# LCD-Input_Module.net
KiCad netlist of a schematic drawn in EAGLE
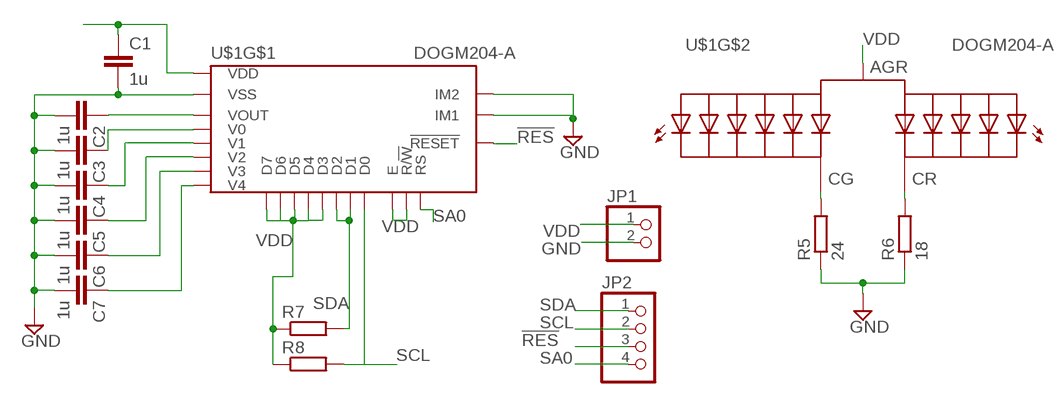
[diagram p0: schematic, sheet 1]
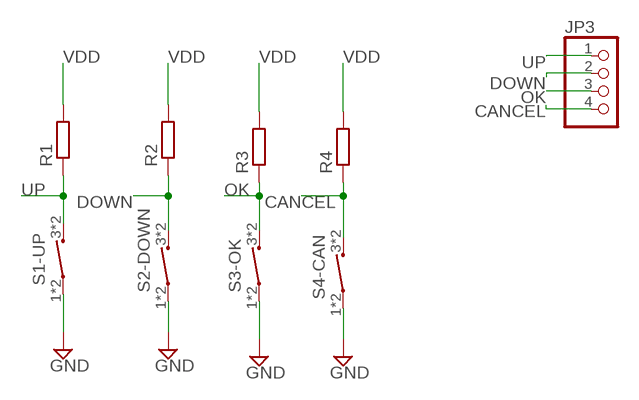
[diagram p1: schematic, sheet 2]

(export (version "E")
  (design (tool "Eeschema 10.0.6"))
  (components
    (comp (ref "C1")
      (value "1u")
      (footprint "eagle-import:C0603")
      (libsource (lib "eagle-import") (part "C-EUC0603"))
    )
    (comp (ref "C2")
      (value "1u")
      (footprint "eagle-import:C0603")
      (libsource (lib "eagle-import") (part "C-EUC0603"))
    )
    (comp (ref "C3")
      (value "1u")
      (footprint "eagle-import:C0603")
      (libsource (lib "eagle-import") (part "C-EUC0603"))
    )
    (comp (ref "C4")
      (value "1u")
      (footprint "eagle-import:C0603")
      (libsource (lib "eagle-import") (part "C-EUC0603"))
    )
    (comp (ref "C5")
      (value "1u")
      (footprint "eagle-import:C0603")
      (libsource (lib "eagle-import") (part "C-EUC0603"))
    )
    (comp (ref "C6")
      (value "1u")
      (footprint "eagle-import:C0603")
      (libsource (lib "eagle-import") (part "C-EUC0603"))
    )
    (comp (ref "C7")
      (value "1u")
      (footprint "eagle-import:C0603")
      (libsource (lib "eagle-import") (part "C-EUC0603"))
    )
    (comp (ref "JP1")
      (value "PINHD-1X2")
      (footprint "eagle-import:1X02")
      (libsource (lib "eagle-import") (part "PINHD-1X2"))
    )
    (comp (ref "JP2")
      (value "PINHD-1X4")
      (footprint "eagle-import:1X04")
      (libsource (lib "eagle-import") (part "PINHD-1X4"))
    )
    (comp (ref "R5")
      (value "24")
      (footprint "eagle-import:R0603")
      (libsource (lib "eagle-import") (part "R-EU_R0603"))
    )
    (comp (ref "R6")
      (value "18")
      (footprint "eagle-import:R0603")
      (libsource (lib "eagle-import") (part "R-EU_R0603"))
    )
    (comp (ref "R7")
      (value "R-EU_R0603")
      (footprint "eagle-import:R0603")
      (libsource (lib "eagle-import") (part "R-EU_R0603"))
    )
    (comp (ref "R8")
      (value "R-EU_R0603")
      (footprint "eagle-import:R0603")
      (libsource (lib "eagle-import") (part "R-EU_R0603"))
    )
    (comp (ref "U$1")
      (value "DOGM204-A")
      (footprint "eagle-import:LCD")
      (libsource (lib "eagle-import") (part "DOGM204-A"))
    )
    (comp (ref "JP3")
      (value "PINHD-1X4")
      (footprint "eagle-import:1X04")
      (libsource (lib "eagle-import") (part "PINHD-1X4"))
    )
    (comp (ref "R1")
      (value "R-EU_R0603")
      (footprint "eagle-import:R0603")
      (libsource (lib "eagle-import") (part "R-EU_R0603"))
    )
    (comp (ref "R2")
      (value "R-EU_R0603")
      (footprint "eagle-import:R0603")
      (libsource (lib "eagle-import") (part "R-EU_R0603"))
    )
    (comp (ref "R3")
      (value "R-EU_R0603")
      (footprint "eagle-import:R0603")
      (libsource (lib "eagle-import") (part "R-EU_R0603"))
    )
    (comp (ref "R4")
      (value "R-EU_R0603")
      (footprint "eagle-import:R0603")
      (libsource (lib "eagle-import") (part "R-EU_R0603"))
    )
    (comp (ref "S1-UP")
      (value "PTS647")
      (footprint "eagle-import:PTS647-TACTSWITCH")
      (libsource (lib "eagle-import") (part "PTS647"))
    )
    (comp (ref "S2-DOWN")
      (value "PTS647")
      (footprint "eagle-import:PTS647-TACTSWITCH")
      (libsource (lib "eagle-import") (part "PTS647"))
    )
    (comp (ref "S3-OK")
      (value "PTS647")
      (footprint "eagle-import:PTS647-TACTSWITCH")
      (libsource (lib "eagle-import") (part "PTS647"))
    )
    (comp (ref "S4-CAN")
      (value "PTS647")
      (footprint "eagle-import:PTS647-TACTSWITCH")
      (libsource (lib "eagle-import") (part "PTS647"))
    )
  )
  (nets
    (net (code "1") (name "CANCEL") (class "Default")
      (node (ref "JP3") (pin "4") (pinfunction "4_4") (pintype "passive"))
      (node (ref "R4") (pin "1") (pinfunction "1_1") (pintype "passive"))
      (node (ref "S4-CAN") (pin "3") (pinfunction "2_3") (pintype "passive"))
      (node (ref "S4-CAN") (pin "4") (pinfunction "2_4") (pintype "passive"))
    )
    (net (code "2") (name "DOWN") (class "Default")
      (node (ref "JP3") (pin "2") (pinfunction "2_2") (pintype "passive"))
      (node (ref "R2") (pin "1") (pinfunction "1_1") (pintype "passive"))
      (node (ref "S2-DOWN") (pin "3") (pinfunction "2_3") (pintype "passive"))
      (node (ref "S2-DOWN") (pin "4") (pinfunction "2_4") (pintype "passive"))
    )
    (net (code "3") (name "GND") (class "Default")
      (node (ref "C1") (pin "2") (pinfunction "2_2") (pintype "passive"))
      (node (ref "C2") (pin "2") (pinfunction "2_2") (pintype "passive"))
      (node (ref "C3") (pin "2") (pinfunction "2_2") (pintype "passive"))
      (node (ref "C4") (pin "2") (pinfunction "2_2") (pintype "passive"))
      (node (ref "C5") (pin "2") (pinfunction "2_2") (pintype "passive"))
      (node (ref "C6") (pin "2") (pinfunction "2_2") (pintype "passive"))
      (node (ref "C7") (pin "2") (pinfunction "2_2") (pintype "passive"))
      (node (ref "JP1") (pin "2") (pinfunction "2_2") (pintype "passive"))
      (node (ref "R5") (pin "1") (pinfunction "1_1") (pintype "passive"))
      (node (ref "R6") (pin "1") (pinfunction "1_1") (pintype "passive"))
      (node (ref "S1-UP") (pin "1") (pinfunction "1_1") (pintype "passive"))
      (node (ref "S1-UP") (pin "2") (pinfunction "1_2") (pintype "passive"))
      (node (ref "S2-DOWN") (pin "1") (pinfunction "1_1") (pintype "passive"))
      (node (ref "S2-DOWN") (pin "2") (pinfunction "1_2") (pintype "passive"))
      (node (ref "S3-OK") (pin "1") (pinfunction "1_1") (pintype "passive"))
      (node (ref "S3-OK") (pin "2") (pinfunction "1_2") (pintype "passive"))
      (node (ref "S4-CAN") (pin "1") (pinfunction "1_1") (pintype "passive"))
      (node (ref "S4-CAN") (pin "2") (pinfunction "1_2") (pintype "passive"))
      (node (ref "U$1") (pin "P$29") (pinfunction "IM2_P$29") (pintype "bidirectional"))
      (node (ref "U$1") (pin "P$30") (pinfunction "IM1_P$30") (pintype "bidirectional"))
      (node (ref "U$1") (pin "P$32") (pinfunction "VSS_P$32") (pintype "bidirectional"))
    )
    (net (code "4") (name "Net-(U$1A-V0)") (class "Default")
      (node (ref "C3") (pin "1") (pinfunction "1_1") (pintype "passive"))
      (node (ref "U$1") (pin "P$24") (pinfunction "V0_P$24") (pintype "bidirectional"))
    )
    (net (code "5") (name "Net-(U$1A-V1)") (class "Default")
      (node (ref "C4") (pin "1") (pinfunction "1_1") (pintype "passive"))
      (node (ref "U$1") (pin "P$25") (pinfunction "V1_P$25") (pintype "bidirectional"))
    )
    (net (code "6") (name "Net-(U$1A-V2)") (class "Default")
      (node (ref "C5") (pin "1") (pinfunction "1_1") (pintype "passive"))
      (node (ref "U$1") (pin "P$26") (pinfunction "V2_P$26") (pintype "bidirectional"))
    )
    (net (code "7") (name "Net-(U$1A-V3)") (class "Default")
      (node (ref "C6") (pin "1") (pinfunction "1_1") (pintype "passive"))
      (node (ref "U$1") (pin "P$27") (pinfunction "V3_P$27") (pintype "bidirectional"))
    )
    (net (code "8") (name "Net-(U$1A-V4)") (class "Default")
      (node (ref "C7") (pin "1") (pinfunction "1_1") (pintype "passive"))
      (node (ref "U$1") (pin "P$28") (pinfunction "V4_P$28") (pintype "bidirectional"))
    )
    (net (code "9") (name "Net-(U$1A-VDD)") (class "Default")
      (node (ref "C1") (pin "1") (pinfunction "1_1") (pintype "passive"))
      (node (ref "U$1") (pin "P$31") (pinfunction "VDD_P$31") (pintype "bidirectional"))
    )
    (net (code "10") (name "Net-(U$1A-VOUT)") (class "Default")
      (node (ref "C2") (pin "1") (pinfunction "1_1") (pintype "passive"))
      (node (ref "U$1") (pin "P$23") (pinfunction "VOUT_P$23") (pintype "bidirectional"))
    )
    (net (code "11") (name "Net-(U$1B-CG)") (class "Default")
      (node (ref "R5") (pin "2") (pinfunction "2_2") (pintype "passive"))
      (node (ref "U$1") (pin "P$21") (pinfunction "CG_P$21") (pintype "passive"))
    )
    (net (code "12") (name "Net-(U$1B-CR)") (class "Default")
      (node (ref "R6") (pin "2") (pinfunction "2_2") (pintype "passive"))
      (node (ref "U$1") (pin "P$22") (pinfunction "CR_P$22") (pintype "passive"))
    )
    (net (code "13") (name "OK") (class "Default")
      (node (ref "JP3") (pin "3") (pinfunction "3_3") (pintype "passive"))
      (node (ref "R3") (pin "1") (pinfunction "1_1") (pintype "passive"))
      (node (ref "S3-OK") (pin "3") (pinfunction "2_3") (pintype "passive"))
      (node (ref "S3-OK") (pin "4") (pinfunction "2_4") (pintype "passive"))
    )
    (net (code "14") (name "SA0") (class "Default")
      (node (ref "JP2") (pin "4") (pinfunction "4_4") (pintype "passive"))
      (node (ref "U$1") (pin "P$43") (pinfunction "RS_P$43") (pintype "bidirectional"))
    )
    (net (code "15") (name "SCL") (class "Default")
      (node (ref "JP2") (pin "2") (pinfunction "2_2") (pintype "passive"))
      (node (ref "R8") (pin "2") (pinfunction "2_2") (pintype "passive"))
      (node (ref "U$1") (pin "P$40") (pinfunction "D0_P$40") (pintype "bidirectional"))
    )
    (net (code "16") (name "SDA") (class "Default")
      (node (ref "JP2") (pin "1") (pinfunction "1_1") (pintype "passive"))
      (node (ref "R7") (pin "2") (pinfunction "2_2") (pintype "passive"))
      (node (ref "U$1") (pin "P$38") (pinfunction "D2_P$38") (pintype "bidirectional"))
      (node (ref "U$1") (pin "P$39") (pinfunction "D1_P$39") (pintype "bidirectional"))
    )
    (net (code "17") (name "UP") (class "Default")
      (node (ref "JP3") (pin "1") (pinfunction "1_1") (pintype "passive"))
      (node (ref "R1") (pin "1") (pinfunction "1_1") (pintype "passive"))
      (node (ref "S1-UP") (pin "3") (pinfunction "2_3") (pintype "passive"))
      (node (ref "S1-UP") (pin "4") (pinfunction "2_4") (pintype "passive"))
    )
    (net (code "18") (name "VDD") (class "Default")
      (node (ref "JP1") (pin "1") (pinfunction "1_1") (pintype "passive"))
      (node (ref "R1") (pin "2") (pinfunction "2_2") (pintype "passive"))
      (node (ref "R2") (pin "2") (pinfunction "2_2") (pintype "passive"))
      (node (ref "R3") (pin "2") (pinfunction "2_2") (pintype "passive"))
      (node (ref "R4") (pin "2") (pinfunction "2_2") (pintype "passive"))
      (node (ref "R7") (pin "1") (pinfunction "1_1") (pintype "passive"))
      (node (ref "R8") (pin "1") (pinfunction "1_1") (pintype "passive"))
      (node (ref "U$1") (pin "P$1") (pinfunction "AGR_P$1") (pintype "passive"))
      (node (ref "U$1") (pin "P$33") (pinfunction "D7_P$33") (pintype "bidirectional"))
      (node (ref "U$1") (pin "P$34") (pinfunction "D6_P$34") (pintype "bidirectional"))
      (node (ref "U$1") (pin "P$35") (pinfunction "D5_P$35") (pintype "bidirectional"))
      (node (ref "U$1") (pin "P$36") (pinfunction "D4_P$36") (pintype "bidirectional"))
      (node (ref "U$1") (pin "P$37") (pinfunction "D3_P$37") (pintype "bidirectional"))
      (node (ref "U$1") (pin "P$41") (pinfunction "E_P$41") (pintype "bidirectional"))
      (node (ref "U$1") (pin "P$42") (pinfunction "R/~{W}_P$42") (pintype "bidirectional"))
    )
    (net (code "19") (name "~{RES}") (class "Default")
      (node (ref "JP2") (pin "3") (pinfunction "3_3") (pintype "passive"))
      (node (ref "U$1") (pin "P$44") (pinfunction "~{RESET}_P$44") (pintype "bidirectional"))
    )
  )
)
